# V6.net
KiCad netlist of a schematic drawn in EAGLE
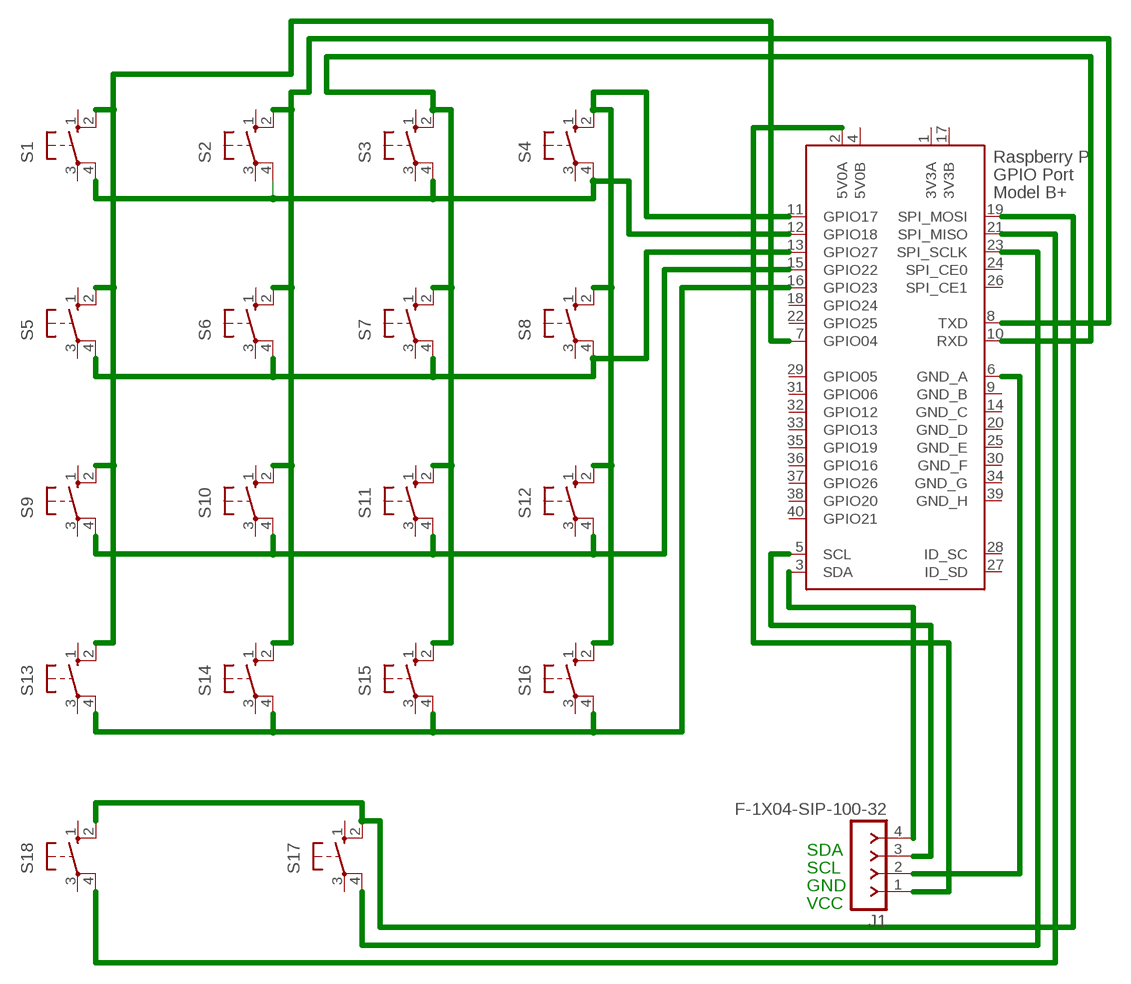
[diagram p0: schematic, sheet 1]

(export (version "E")
  (design (tool "Eeschema 10.0.6"))
  (components
    (comp (ref "J1")
      (value "F-1X04-SIP-100-32")
      (footprint "eagle-import:SIP-100-04-32")
      (libsource (lib "eagle-import") (part "F-1X04-SIP-100-32"))
    )
    (comp (ref "S1")
      (value "40-XX")
      (footprint "eagle-import:B3F-40XX")
      (fields (field (name "MF") "OMRON COMPONENTS USA") (field (name "MPN") "B3F-4000"))
      (libsource (lib "eagle-import") (part "40-XX"))
    )
    (comp (ref "S2")
      (value "40-XX")
      (footprint "eagle-import:B3F-40XX")
      (fields (field (name "MF") "OMRON COMPONENTS USA") (field (name "MPN") "B3F-4000"))
      (libsource (lib "eagle-import") (part "40-XX"))
    )
    (comp (ref "S3")
      (value "40-XX")
      (footprint "eagle-import:B3F-40XX")
      (fields (field (name "MF") "OMRON COMPONENTS USA") (field (name "MPN") "B3F-4000"))
      (libsource (lib "eagle-import") (part "40-XX"))
    )
    (comp (ref "S4")
      (value "40-XX")
      (footprint "eagle-import:B3F-40XX")
      (fields (field (name "MF") "OMRON COMPONENTS USA") (field (name "MPN") "B3F-4000"))
      (libsource (lib "eagle-import") (part "40-XX"))
    )
    (comp (ref "S5")
      (value "40-XX")
      (footprint "eagle-import:B3F-40XX")
      (fields (field (name "MF") "OMRON COMPONENTS USA") (field (name "MPN") "B3F-4000"))
      (libsource (lib "eagle-import") (part "40-XX"))
    )
    (comp (ref "S6")
      (value "40-XX")
      (footprint "eagle-import:B3F-40XX")
      (fields (field (name "MF") "OMRON COMPONENTS USA") (field (name "MPN") "B3F-4000"))
      (libsource (lib "eagle-import") (part "40-XX"))
    )
    (comp (ref "S7")
      (value "40-XX")
      (footprint "eagle-import:B3F-40XX")
      (fields (field (name "MF") "OMRON COMPONENTS USA") (field (name "MPN") "B3F-4000"))
      (libsource (lib "eagle-import") (part "40-XX"))
    )
    (comp (ref "S8")
      (value "40-XX")
      (footprint "eagle-import:B3F-40XX")
      (fields (field (name "MF") "OMRON COMPONENTS USA") (field (name "MPN") "B3F-4000"))
      (libsource (lib "eagle-import") (part "40-XX"))
    )
    (comp (ref "S9")
      (value "40-XX")
      (footprint "eagle-import:B3F-40XX")
      (fields (field (name "MF") "OMRON COMPONENTS USA") (field (name "MPN") "B3F-4000"))
      (libsource (lib "eagle-import") (part "40-XX"))
    )
    (comp (ref "S10")
      (value "40-XX")
      (footprint "eagle-import:B3F-40XX")
      (fields (field (name "MF") "OMRON COMPONENTS USA") (field (name "MPN") "B3F-4000"))
      (libsource (lib "eagle-import") (part "40-XX"))
    )
    (comp (ref "S11")
      (value "40-XX")
      (footprint "eagle-import:B3F-40XX")
      (fields (field (name "MF") "OMRON COMPONENTS USA") (field (name "MPN") "B3F-4000"))
      (libsource (lib "eagle-import") (part "40-XX"))
    )
    (comp (ref "S12")
      (value "40-XX")
      (footprint "eagle-import:B3F-40XX")
      (fields (field (name "MF") "OMRON COMPONENTS USA") (field (name "MPN") "B3F-4000"))
      (libsource (lib "eagle-import") (part "40-XX"))
    )
    (comp (ref "S13")
      (value "40-XX")
      (footprint "eagle-import:B3F-40XX")
      (fields (field (name "MF") "OMRON COMPONENTS USA") (field (name "MPN") "B3F-4000"))
      (libsource (lib "eagle-import") (part "40-XX"))
    )
    (comp (ref "S14")
      (value "40-XX")
      (footprint "eagle-import:B3F-40XX")
      (fields (field (name "MF") "OMRON COMPONENTS USA") (field (name "MPN") "B3F-4000"))
      (libsource (lib "eagle-import") (part "40-XX"))
    )
    (comp (ref "S15")
      (value "40-XX")
      (footprint "eagle-import:B3F-40XX")
      (fields (field (name "MF") "OMRON COMPONENTS USA") (field (name "MPN") "B3F-4000"))
      (libsource (lib "eagle-import") (part "40-XX"))
    )
    (comp (ref "S16")
      (value "40-XX")
      (footprint "eagle-import:B3F-40XX")
      (fields (field (name "MF") "OMRON COMPONENTS USA") (field (name "MPN") "B3F-4000"))
      (libsource (lib "eagle-import") (part "40-XX"))
    )
    (comp (ref "S17")
      (value "40-XX")
      (footprint "eagle-import:B3F-40XX")
      (fields (field (name "MF") "OMRON COMPONENTS USA") (field (name "MPN") "B3F-4000"))
      (libsource (lib "eagle-import") (part "40-XX"))
    )
    (comp (ref "S18")
      (value "40-XX")
      (footprint "eagle-import:B3F-40XX")
      (fields (field (name "MF") "OMRON COMPONENTS USA") (field (name "MPN") "B3F-4000"))
      (libsource (lib "eagle-import") (part "40-XX"))
    )
    (comp (ref "X1")
      (value "RASPI_GPIO_B+#_PIN")
      (footprint "eagle-import:RASPI_GPIO_B+_PIN")
      (libsource (lib "eagle-import") (part "RASPI_GPIO_B+#_PIN"))
    )
  )
  (nets
    (net (code "1") (name "/3V3A") (class "Default")
      (node (ref "X1") (pin "1") (pinfunction "3V3A_1") (pintype "power_in"))
    )
    (net (code "2") (name "/3V3B") (class "Default")
      (node (ref "X1") (pin "17") (pinfunction "3V3B_17") (pintype "power_in"))
    )
    (net (code "3") (name "/5V0B") (class "Default")
      (node (ref "X1") (pin "4") (pinfunction "5V0B_4") (pintype "power_in"))
    )
    (net (code "4") (name "/GND_B") (class "Default")
      (node (ref "X1") (pin "9") (pinfunction "GND_B_9") (pintype "power_in"))
    )
    (net (code "5") (name "/GND_C") (class "Default")
      (node (ref "X1") (pin "14") (pinfunction "GND_C_14") (pintype "power_in"))
    )
    (net (code "6") (name "/GND_D") (class "Default")
      (node (ref "X1") (pin "20") (pinfunction "GND_D_20") (pintype "power_in"))
    )
    (net (code "7") (name "/GND_E") (class "Default")
      (node (ref "X1") (pin "25") (pinfunction "GND_E_25") (pintype "power_in"))
    )
    (net (code "8") (name "/GND_F") (class "Default")
      (node (ref "X1") (pin "30") (pinfunction "GND_F_30") (pintype "power_in"))
    )
    (net (code "9") (name "/GND_G") (class "Default")
      (node (ref "X1") (pin "34") (pinfunction "GND_G_34") (pintype "power_in"))
    )
    (net (code "10") (name "/GND_H") (class "Default")
      (node (ref "X1") (pin "39") (pinfunction "GND_H_39") (pintype "power_in"))
    )
    (net (code "11") (name "Net-(S1-P1)") (class "Default")
      (node (ref "S1") (pin "4") (pinfunction "P1_4") (pintype "passive"))
      (node (ref "S2") (pin "4") (pinfunction "P1_4") (pintype "passive"))
      (node (ref "S3") (pin "4") (pinfunction "P1_4") (pintype "passive"))
      (node (ref "S4") (pin "4") (pinfunction "P1_4") (pintype "passive"))
      (node (ref "X1") (pin "12") (pinfunction "GPIO18_12") (pintype "bidirectional"))
    )
    (net (code "12") (name "Net-(S1-S1)") (class "Default")
      (node (ref "S1") (pin "2") (pinfunction "S1_2") (pintype "passive"))
      (node (ref "S13") (pin "2") (pinfunction "S1_2") (pintype "passive"))
      (node (ref "S5") (pin "2") (pinfunction "S1_2") (pintype "passive"))
      (node (ref "S9") (pin "2") (pinfunction "S1_2") (pintype "passive"))
      (node (ref "X1") (pin "7") (pinfunction "GPIO04_7") (pintype "bidirectional"))
    )
    (net (code "13") (name "Net-(S5-P1)") (class "Default")
      (node (ref "S5") (pin "4") (pinfunction "P1_4") (pintype "passive"))
      (node (ref "S6") (pin "4") (pinfunction "P1_4") (pintype "passive"))
      (node (ref "S7") (pin "4") (pinfunction "P1_4") (pintype "passive"))
      (node (ref "S8") (pin "4") (pinfunction "P1_4") (pintype "passive"))
      (node (ref "X1") (pin "13") (pinfunction "GPIO27_13") (pintype "bidirectional"))
    )
    (net (code "14") (name "Net-(S10-P1)") (class "Default")
      (node (ref "S10") (pin "4") (pinfunction "P1_4") (pintype "passive"))
      (node (ref "S11") (pin "4") (pinfunction "P1_4") (pintype "passive"))
      (node (ref "S12") (pin "4") (pinfunction "P1_4") (pintype "passive"))
      (node (ref "S9") (pin "4") (pinfunction "P1_4") (pintype "passive"))
      (node (ref "X1") (pin "15") (pinfunction "GPIO22_15") (pintype "bidirectional"))
    )
    (net (code "15") (name "Net-(S10-S1)") (class "Default")
      (node (ref "S10") (pin "2") (pinfunction "S1_2") (pintype "passive"))
      (node (ref "S14") (pin "2") (pinfunction "S1_2") (pintype "passive"))
      (node (ref "S2") (pin "2") (pinfunction "S1_2") (pintype "passive"))
      (node (ref "S6") (pin "2") (pinfunction "S1_2") (pintype "passive"))
      (node (ref "X1") (pin "8") (pinfunction "TXD_8") (pintype "bidirectional"))
    )
    (net (code "16") (name "Net-(S11-S1)") (class "Default")
      (node (ref "S11") (pin "2") (pinfunction "S1_2") (pintype "passive"))
      (node (ref "S15") (pin "2") (pinfunction "S1_2") (pintype "passive"))
      (node (ref "S3") (pin "2") (pinfunction "S1_2") (pintype "passive"))
      (node (ref "S7") (pin "2") (pinfunction "S1_2") (pintype "passive"))
      (node (ref "X1") (pin "10") (pinfunction "RXD_10") (pintype "bidirectional"))
    )
    (net (code "17") (name "Net-(S12-S1)") (class "Default")
      (node (ref "S12") (pin "2") (pinfunction "S1_2") (pintype "passive"))
      (node (ref "S16") (pin "2") (pinfunction "S1_2") (pintype "passive"))
      (node (ref "S4") (pin "2") (pinfunction "S1_2") (pintype "passive"))
      (node (ref "S8") (pin "2") (pinfunction "S1_2") (pintype "passive"))
      (node (ref "X1") (pin "11") (pinfunction "GPIO17_11") (pintype "bidirectional"))
    )
    (net (code "18") (name "Net-(S13-P1)") (class "Default")
      (node (ref "S13") (pin "4") (pinfunction "P1_4") (pintype "passive"))
      (node (ref "S14") (pin "4") (pinfunction "P1_4") (pintype "passive"))
      (node (ref "S15") (pin "4") (pinfunction "P1_4") (pintype "passive"))
      (node (ref "S16") (pin "4") (pinfunction "P1_4") (pintype "passive"))
      (node (ref "X1") (pin "16") (pinfunction "GPIO23_16") (pintype "bidirectional"))
    )
    (net (code "19") (name "Net-(S17-P1)") (class "Default")
      (node (ref "S17") (pin "4") (pinfunction "P1_4") (pintype "passive"))
      (node (ref "X1") (pin "23") (pinfunction "SPI_SCLK_23") (pintype "bidirectional"))
    )
    (net (code "20") (name "Net-(S17-S1)") (class "Default")
      (node (ref "S17") (pin "2") (pinfunction "S1_2") (pintype "passive"))
      (node (ref "S18") (pin "2") (pinfunction "S1_2") (pintype "passive"))
      (node (ref "X1") (pin "19") (pinfunction "SPI_MOSI_19") (pintype "bidirectional"))
    )
    (net (code "21") (name "Net-(S18-P1)") (class "Default")
      (node (ref "S18") (pin "4") (pinfunction "P1_4") (pintype "passive"))
      (node (ref "X1") (pin "21") (pinfunction "SPI_MISO_21") (pintype "bidirectional"))
    )
    (net (code "22") (name "Net-(X1-5V0A)") (class "Default")
      (node (ref "J1") (pin "1") (pinfunction "1_1") (pintype "passive"))
      (node (ref "X1") (pin "2") (pinfunction "5V0A_2") (pintype "power_in"))
    )
    (net (code "23") (name "Net-(X1-GND_A)") (class "Default")
      (node (ref "J1") (pin "2") (pinfunction "2_2") (pintype "passive"))
      (node (ref "X1") (pin "6") (pinfunction "GND_A_6") (pintype "power_in"))
    )
    (net (code "24") (name "Net-(X1-SCL)") (class "Default")
      (node (ref "J1") (pin "3") (pinfunction "3_3") (pintype "passive"))
      (node (ref "X1") (pin "5") (pinfunction "SCL_5") (pintype "bidirectional"))
    )
    (net (code "25") (name "Net-(X1-SDA)") (class "Default")
      (node (ref "J1") (pin "4") (pinfunction "4_4") (pintype "passive"))
      (node (ref "X1") (pin "3") (pinfunction "SDA_3") (pintype "bidirectional"))
    )
    (net (code "26") (name "unconnected-(S1-P-Pad3)") (class "Default")
      (node (ref "S1") (pin "3") (pinfunction "P_3") (pintype "passive"))
    )
    (net (code "27") (name "unconnected-(S1-S-Pad1)") (class "Default")
      (node (ref "S1") (pin "1") (pinfunction "S_1") (pintype "passive"))
    )
    (net (code "28") (name "unconnected-(S2-P-Pad3)") (class "Default")
      (node (ref "S2") (pin "3") (pinfunction "P_3") (pintype "passive"))
    )
    (net (code "29") (name "unconnected-(S2-S-Pad1)") (class "Default")
      (node (ref "S2") (pin "1") (pinfunction "S_1") (pintype "passive"))
    )
    (net (code "30") (name "unconnected-(S3-P-Pad3)") (class "Default")
      (node (ref "S3") (pin "3") (pinfunction "P_3") (pintype "passive"))
    )
    (net (code "31") (name "unconnected-(S3-S-Pad1)") (class "Default")
      (node (ref "S3") (pin "1") (pinfunction "S_1") (pintype "passive"))
    )
    (net (code "32") (name "unconnected-(S4-P-Pad3)") (class "Default")
      (node (ref "S4") (pin "3") (pinfunction "P_3") (pintype "passive"))
    )
    (net (code "33") (name "unconnected-(S4-S-Pad1)") (class "Default")
      (node (ref "S4") (pin "1") (pinfunction "S_1") (pintype "passive"))
    )
    (net (code "34") (name "unconnected-(S5-P-Pad3)") (class "Default")
      (node (ref "S5") (pin "3") (pinfunction "P_3") (pintype "passive"))
    )
    (net (code "35") (name "unconnected-(S5-S-Pad1)") (class "Default")
      (node (ref "S5") (pin "1") (pinfunction "S_1") (pintype "passive"))
    )
    (net (code "36") (name "unconnected-(S6-P-Pad3)") (class "Default")
      (node (ref "S6") (pin "3") (pinfunction "P_3") (pintype "passive"))
    )
    (net (code "37") (name "unconnected-(S6-S-Pad1)") (class "Default")
      (node (ref "S6") (pin "1") (pinfunction "S_1") (pintype "passive"))
    )
    (net (code "38") (name "unconnected-(S7-P-Pad3)") (class "Default")
      (node (ref "S7") (pin "3") (pinfunction "P_3") (pintype "passive"))
    )
    (net (code "39") (name "unconnected-(S7-S-Pad1)") (class "Default")
      (node (ref "S7") (pin "1") (pinfunction "S_1") (pintype "passive"))
    )
    (net (code "40") (name "unconnected-(S8-P-Pad3)") (class "Default")
      (node (ref "S8") (pin "3") (pinfunction "P_3") (pintype "passive"))
    )
    (net (code "41") (name "unconnected-(S8-S-Pad1)") (class "Default")
      (node (ref "S8") (pin "1") (pinfunction "S_1") (pintype "passive"))
    )
    (net (code "42") (name "unconnected-(S9-P-Pad3)") (class "Default")
      (node (ref "S9") (pin "3") (pinfunction "P_3") (pintype "passive"))
    )
    (net (code "43") (name "unconnected-(S9-S-Pad1)") (class "Default")
      (node (ref "S9") (pin "1") (pinfunction "S_1") (pintype "passive"))
    )
    (net (code "44") (name "unconnected-(S10-P-Pad3)") (class "Default")
      (node (ref "S10") (pin "3") (pinfunction "P_3") (pintype "passive"))
    )
    (net (code "45") (name "unconnected-(S10-S-Pad1)") (class "Default")
      (node (ref "S10") (pin "1") (pinfunction "S_1") (pintype "passive"))
    )
    (net (code "46") (name "unconnected-(S11-P-Pad3)") (class "Default")
      (node (ref "S11") (pin "3") (pinfunction "P_3") (pintype "passive"))
    )
    (net (code "47") (name "unconnected-(S11-S-Pad1)") (class "Default")
      (node (ref "S11") (pin "1") (pinfunction "S_1") (pintype "passive"))
    )
    (net (code "48") (name "unconnected-(S12-P-Pad3)") (class "Default")
      (node (ref "S12") (pin "3") (pinfunction "P_3") (pintype "passive"))
    )
    (net (code "49") (name "unconnected-(S12-S-Pad1)") (class "Default")
      (node (ref "S12") (pin "1") (pinfunction "S_1") (pintype "passive"))
    )
    (net (code "50") (name "unconnected-(S13-P-Pad3)") (class "Default")
      (node (ref "S13") (pin "3") (pinfunction "P_3") (pintype "passive"))
    )
    (net (code "51") (name "unconnected-(S13-S-Pad1)") (class "Default")
      (node (ref "S13") (pin "1") (pinfunction "S_1") (pintype "passive"))
    )
    (net (code "52") (name "unconnected-(S14-P-Pad3)") (class "Default")
      (node (ref "S14") (pin "3") (pinfunction "P_3") (pintype "passive"))
    )
    (net (code "53") (name "unconnected-(S14-S-Pad1)") (class "Default")
      (node (ref "S14") (pin "1") (pinfunction "S_1") (pintype "passive"))
    )
    (net (code "54") (name "unconnected-(S15-P-Pad3)") (class "Default")
      (node (ref "S15") (pin "3") (pinfunction "P_3") (pintype "passive"))
    )
    (net (code "55") (name "unconnected-(S15-S-Pad1)") (class "Default")
      (node (ref "S15") (pin "1") (pinfunction "S_1") (pintype "passive"))
    )
    (net (code "56") (name "unconnected-(S16-P-Pad3)") (class "Default")
      (node (ref "S16") (pin "3") (pinfunction "P_3") (pintype "passive"))
    )
    (net (code "57") (name "unconnected-(S16-S-Pad1)") (class "Default")
      (node (ref "S16") (pin "1") (pinfunction "S_1") (pintype "passive"))
    )
    (net (code "58") (name "unconnected-(S17-P-Pad3)") (class "Default")
      (node (ref "S17") (pin "3") (pinfunction "P_3") (pintype "passive"))
    )
    (net (code "59") (name "unconnected-(S17-S-Pad1)") (class "Default")
      (node (ref "S17") (pin "1") (pinfunction "S_1") (pintype "passive"))
    )
    (net (code "60") (name "unconnected-(S18-P-Pad3)") (class "Default")
      (node (ref "S18") (pin "3") (pinfunction "P_3") (pintype "passive"))
    )
    (net (code "61") (name "unconnected-(S18-S-Pad1)") (class "Default")
      (node (ref "S18") (pin "1") (pinfunction "S_1") (pintype "passive"))
    )
    (net (code "62") (name "unconnected-(X1-GPIO05-Pad29)") (class "Default")
      (node (ref "X1") (pin "29") (pinfunction "GPIO05_29") (pintype "no_connect"))
    )
    (net (code "63") (name "unconnected-(X1-GPIO06-Pad31)") (class "Default")
      (node (ref "X1") (pin "31") (pinfunction "GPIO06_31") (pintype "no_connect"))
    )
    (net (code "64") (name "unconnected-(X1-GPIO12-Pad32)") (class "Default")
      (node (ref "X1") (pin "32") (pinfunction "GPIO12_32") (pintype "no_connect"))
    )
    (net (code "65") (name "unconnected-(X1-GPIO13-Pad33)") (class "Default")
      (node (ref "X1") (pin "33") (pinfunction "GPIO13_33") (pintype "no_connect"))
    )
    (net (code "66") (name "unconnected-(X1-GPIO16-Pad36)") (class "Default")
      (node (ref "X1") (pin "36") (pinfunction "GPIO16_36") (pintype "no_connect"))
    )
    (net (code "67") (name "unconnected-(X1-GPIO19-Pad35)") (class "Default")
      (node (ref "X1") (pin "35") (pinfunction "GPIO19_35") (pintype "no_connect"))
    )
    (net (code "68") (name "unconnected-(X1-GPIO20-Pad38)") (class "Default")
      (node (ref "X1") (pin "38") (pinfunction "GPIO20_38") (pintype "no_connect"))
    )
    (net (code "69") (name "unconnected-(X1-GPIO21-Pad40)") (class "Default")
      (node (ref "X1") (pin "40") (pinfunction "GPIO21_40") (pintype "no_connect"))
    )
    (net (code "70") (name "unconnected-(X1-GPIO24-Pad18)") (class "Default")
      (node (ref "X1") (pin "18") (pinfunction "GPIO24_18") (pintype "bidirectional"))
    )
    (net (code "71") (name "unconnected-(X1-GPIO25-Pad22)") (class "Default")
      (node (ref "X1") (pin "22") (pinfunction "GPIO25_22") (pintype "bidirectional"))
    )
    (net (code "72") (name "unconnected-(X1-GPIO26-Pad37)") (class "Default")
      (node (ref "X1") (pin "37") (pinfunction "GPIO26_37") (pintype "no_connect"))
    )
    (net (code "73") (name "unconnected-(X1-ID_SC-Pad28)") (class "Default")
      (node (ref "X1") (pin "28") (pinfunction "ID_SC_28") (pintype "no_connect"))
    )
    (net (code "74") (name "unconnected-(X1-ID_SD-Pad27)") (class "Default")
      (node (ref "X1") (pin "27") (pinfunction "ID_SD_27") (pintype "no_connect"))
    )
    (net (code "75") (name "unconnected-(X1-SPI_CE0-Pad24)") (class "Default")
      (node (ref "X1") (pin "24") (pinfunction "SPI_CE0_24") (pintype "bidirectional"))
    )
    (net (code "76") (name "unconnected-(X1-SPI_CE1-Pad26)") (class "Default")
      (node (ref "X1") (pin "26") (pinfunction "SPI_CE1_26") (pintype "bidirectional"))
    )
  )
)
